# Power.net
KiCad netlist of a schematic drawn in Altium Designer
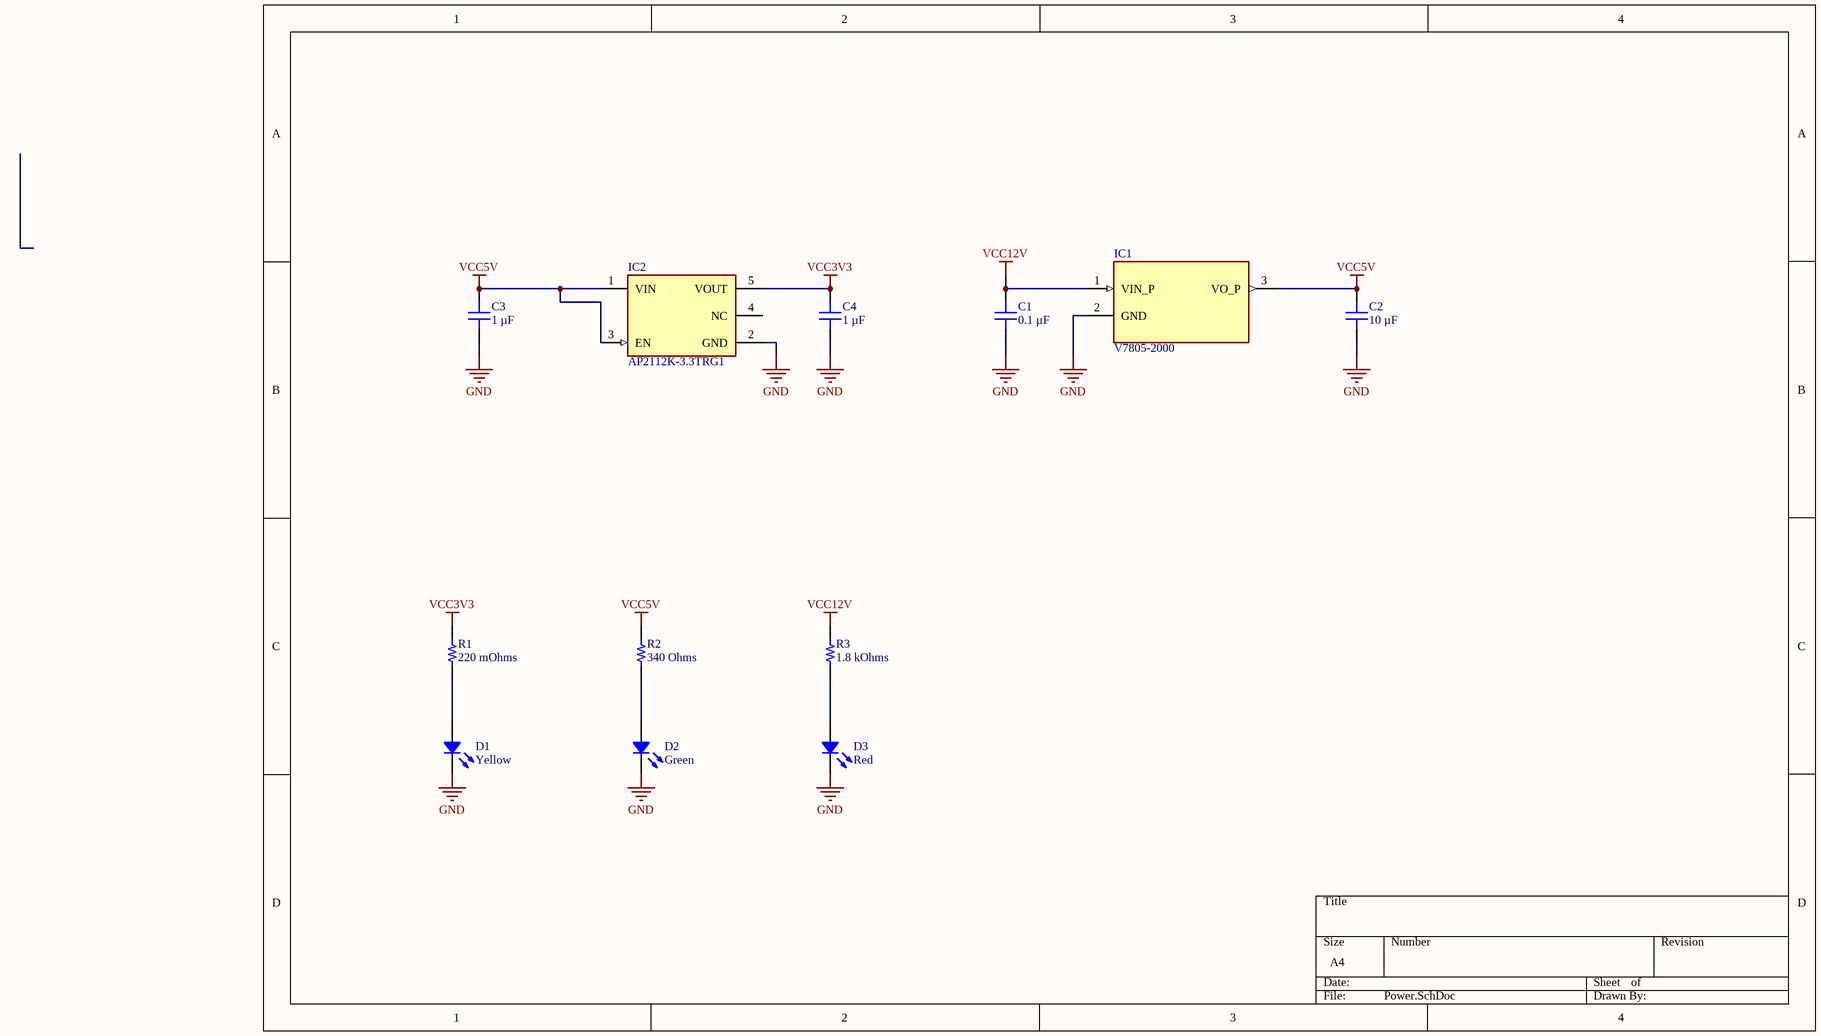
[diagram p0: Power.SchDoc]

(export (version "E")
  (design (tool "Eeschema 10.0.6"))
  (components
    (comp (ref "C1")
      (value "0.1 µF")
      (footprint "CAP 0201_0603")
      (description "CAP CER 0.1UF 16V X5R 0201")
      (fields (field (name "PART NUMBER") "EMK063BJ104MP-F") (field (name "MANUFACTURER") "Taiyo Yuden"))
      (libsource (lib "Celestial Altium Library - altium_library") (part "Capacitor"))
    )
    (comp (ref "C2")
      (value "10 µF")
      (footprint "CAP 0402_1005")
      (description "CAP CER 10UF 10V X5R 0402")
      (fields
        (field (name "PART NUMBER") "CL05A106MP8NUB8")
        (field (name "MANUFACTURER") "Samsung Electro-Mechanics")
      )
      (libsource (lib "Celestial Altium Library - altium_library") (part "Capacitor"))
    )
    (comp (ref "C3")
      (value "1 µF")
      (footprint "CAP 0201_0603")
      (description "CAP CER 1UF 6.3V X5R 0201")
      (fields
        (field (name "PART NUMBER") "CL03A105MQ3CSNC")
        (field (name "MANUFACTURER") "Samsung Electro-Mechanics")
      )
      (libsource (lib "Celestial Altium Library - altium_library") (part "Capacitor"))
    )
    (comp (ref "C4")
      (value "1 µF")
      (footprint "CAP 0201_0603")
      (description "CAP CER 1UF 6.3V X5R 0201")
      (fields
        (field (name "PART NUMBER") "CL03A105MQ3CSNC")
        (field (name "MANUFACTURER") "Samsung Electro-Mechanics")
      )
      (libsource (lib "Celestial Altium Library - altium_library") (part "Capacitor"))
    )
    (comp (ref "D1")
      (value "Yellow")
      (footprint "LED 1206_3216 YELLOW")
      (description "LED YELLOW CLEAR 2SMD")
      (fields
        (field (name "PART NUMBER") "25-21UYC/S530-A2/TR8")
        (field (name "MANUFACTURER") "Everlight Electronics Co Ltd")
      )
      (libsource (lib "Celestial Altium Library - altium_library") (part "LED"))
    )
    (comp (ref "D2")
      (value "Green")
      (footprint "LED 0805_2012 GREEN")
      (description "LED GREEN CLEAR 0805 SMD")
      (fields
        (field (name "PART NUMBER") "QTLP630C4TR")
        (field (name "MANUFACTURER") "Everlight Electronics Co Ltd")
      )
      (libsource (lib "Celestial Altium Library - altium_library") (part "LED"))
    )
    (comp (ref "D3")
      (value "Red")
      (footprint "LED 1206_3216 RED")
      (description "LED RED CLEAR 2SMD")
      (fields (field (name "PART NUMBER") "XZMDK55W-A2RT") (field (name "MANUFACTURER") "SunLED"))
      (libsource (lib "Celestial Altium Library - altium_library") (part "LED"))
    )
    (comp (ref "IC1")
      (value "V7805-2000")
      (footprint "CONV_V7805-2000")
      (description "2 A Output Current, 4.75~18 Vdc Input, 3 Pin SIP, Non-Isolated, Dc-Dc Converter")
      (fields (field (name "DIGI-KEY_PART_NUMBER") "102-2188-ND") (field (name "MF") "CUI Inc."))
      (libsource (lib "V7805-2000") (part "V7805-2000"))
    )
    (comp (ref "IC2")
      (value "AP2112K-3.3TRG1")
      (footprint "FP-SOT25-IPC_A")
      (description "IC REG LINEAR 3.3V 600MA SOT25")
      (libsource (lib "Altium Content Vault") (part "c8ab751aee5229183125ab046a11caa"))
    )
    (comp (ref "R1")
      (value "220 mOhms")
      (footprint "RES 0201_0603")
      (description "RES 0.22 OHM 1% 1/10W 0201")
      (fields
        (field (name "PART NUMBER") "UCR006YVPFLR220")
        (field (name "MANUFACTURER") "Rohm Semiconductor")
      )
      (libsource (lib "Celestial Altium Library - altium_library") (part "Resistor"))
    )
    (comp (ref "R2")
      (value "340 Ohms")
      (footprint "RES 0201_0603")
      (description "RES SMD 340 OHM 1% 1/20W 0201")
      (fields (field (name "PART NUMBER") "AC0201FR-07340RL") (field (name "MANUFACTURER") "Yageo"))
      (libsource (lib "Celestial Altium Library - altium_library") (part "Resistor"))
    )
    (comp (ref "R3")
      (value "1.8 kOhms")
      (footprint "RES 0201_0603")
      (description "RES SMD 1.8K OHM 5% 1/20W 0201")
      (fields (field (name "PART NUMBER") "CRCW02011K80JNED") (field (name "MANUFACTURER") "Vishay Dale"))
      (libsource (lib "Celestial Altium Library - altium_library") (part "Resistor"))
    )
  )
  (nets
    (net (code "1") (name "GND") (class "Default")
      (node (ref "C1") (pin "1") (pinfunction "1_1") (pintype "passive"))
      (node (ref "C2") (pin "1") (pinfunction "1_1") (pintype "passive"))
      (node (ref "C3") (pin "1") (pinfunction "1_1") (pintype "passive"))
      (node (ref "C4") (pin "1") (pinfunction "1_1") (pintype "passive"))
      (node (ref "D1") (pin "2") (pinfunction "2_2") (pintype "passive"))
      (node (ref "D2") (pin "2") (pinfunction "2_2") (pintype "passive"))
      (node (ref "D3") (pin "2") (pinfunction "2_2") (pintype "passive"))
      (node (ref "IC1") (pin "2") (pinfunction "GND_2") (pintype "power_in"))
      (node (ref "IC2") (pin "2") (pinfunction "GND_2") (pintype "power_in"))
    )
    (net (code "2") (name "Net-(D1-Pad1)") (class "Default")
      (node (ref "D1") (pin "1") (pinfunction "1_1") (pintype "passive"))
      (node (ref "R1") (pin "1") (pinfunction "1_1") (pintype "passive"))
    )
    (net (code "3") (name "Net-(D2-Pad1)") (class "Default")
      (node (ref "D2") (pin "1") (pinfunction "1_1") (pintype "passive"))
      (node (ref "R2") (pin "1") (pinfunction "1_1") (pintype "passive"))
    )
    (net (code "4") (name "Net-(D3-Pad1)") (class "Default")
      (node (ref "D3") (pin "1") (pinfunction "1_1") (pintype "passive"))
      (node (ref "R3") (pin "1") (pinfunction "1_1") (pintype "passive"))
    )
    (net (code "5") (name "VCC3V3") (class "Default")
      (node (ref "C4") (pin "2") (pinfunction "2_2") (pintype "passive"))
      (node (ref "IC2") (pin "5") (pinfunction "VOUT_5") (pintype "power_in"))
      (node (ref "R1") (pin "2") (pinfunction "2_2") (pintype "passive"))
    )
    (net (code "6") (name "VCC5V") (class "Default")
      (node (ref "C2") (pin "2") (pinfunction "2_2") (pintype "passive"))
      (node (ref "C3") (pin "2") (pinfunction "2_2") (pintype "passive"))
      (node (ref "IC1") (pin "3") (pinfunction "VO_P_3") (pintype "output"))
      (node (ref "IC2") (pin "1") (pinfunction "VIN_1") (pintype "power_in"))
      (node (ref "IC2") (pin "3") (pinfunction "EN_3") (pintype "input"))
      (node (ref "R2") (pin "2") (pinfunction "2_2") (pintype "passive"))
    )
    (net (code "7") (name "VCC12V") (class "Default")
      (node (ref "C1") (pin "2") (pinfunction "2_2") (pintype "passive"))
      (node (ref "IC1") (pin "1") (pinfunction "VIN_P_1") (pintype "input"))
      (node (ref "R3") (pin "2") (pinfunction "2_2") (pintype "passive"))
    )
    (net (code "8") (name "unconnected-(IC2-NC-Pad4)") (class "Default")
      (node (ref "IC2") (pin "4") (pinfunction "NC_4") (pintype "passive"))
    )
  )
)
